# LPCB235_-_SPI_UART_-_GROUP_A.net
KiCad netlist of a schematic drawn in Altium Designer
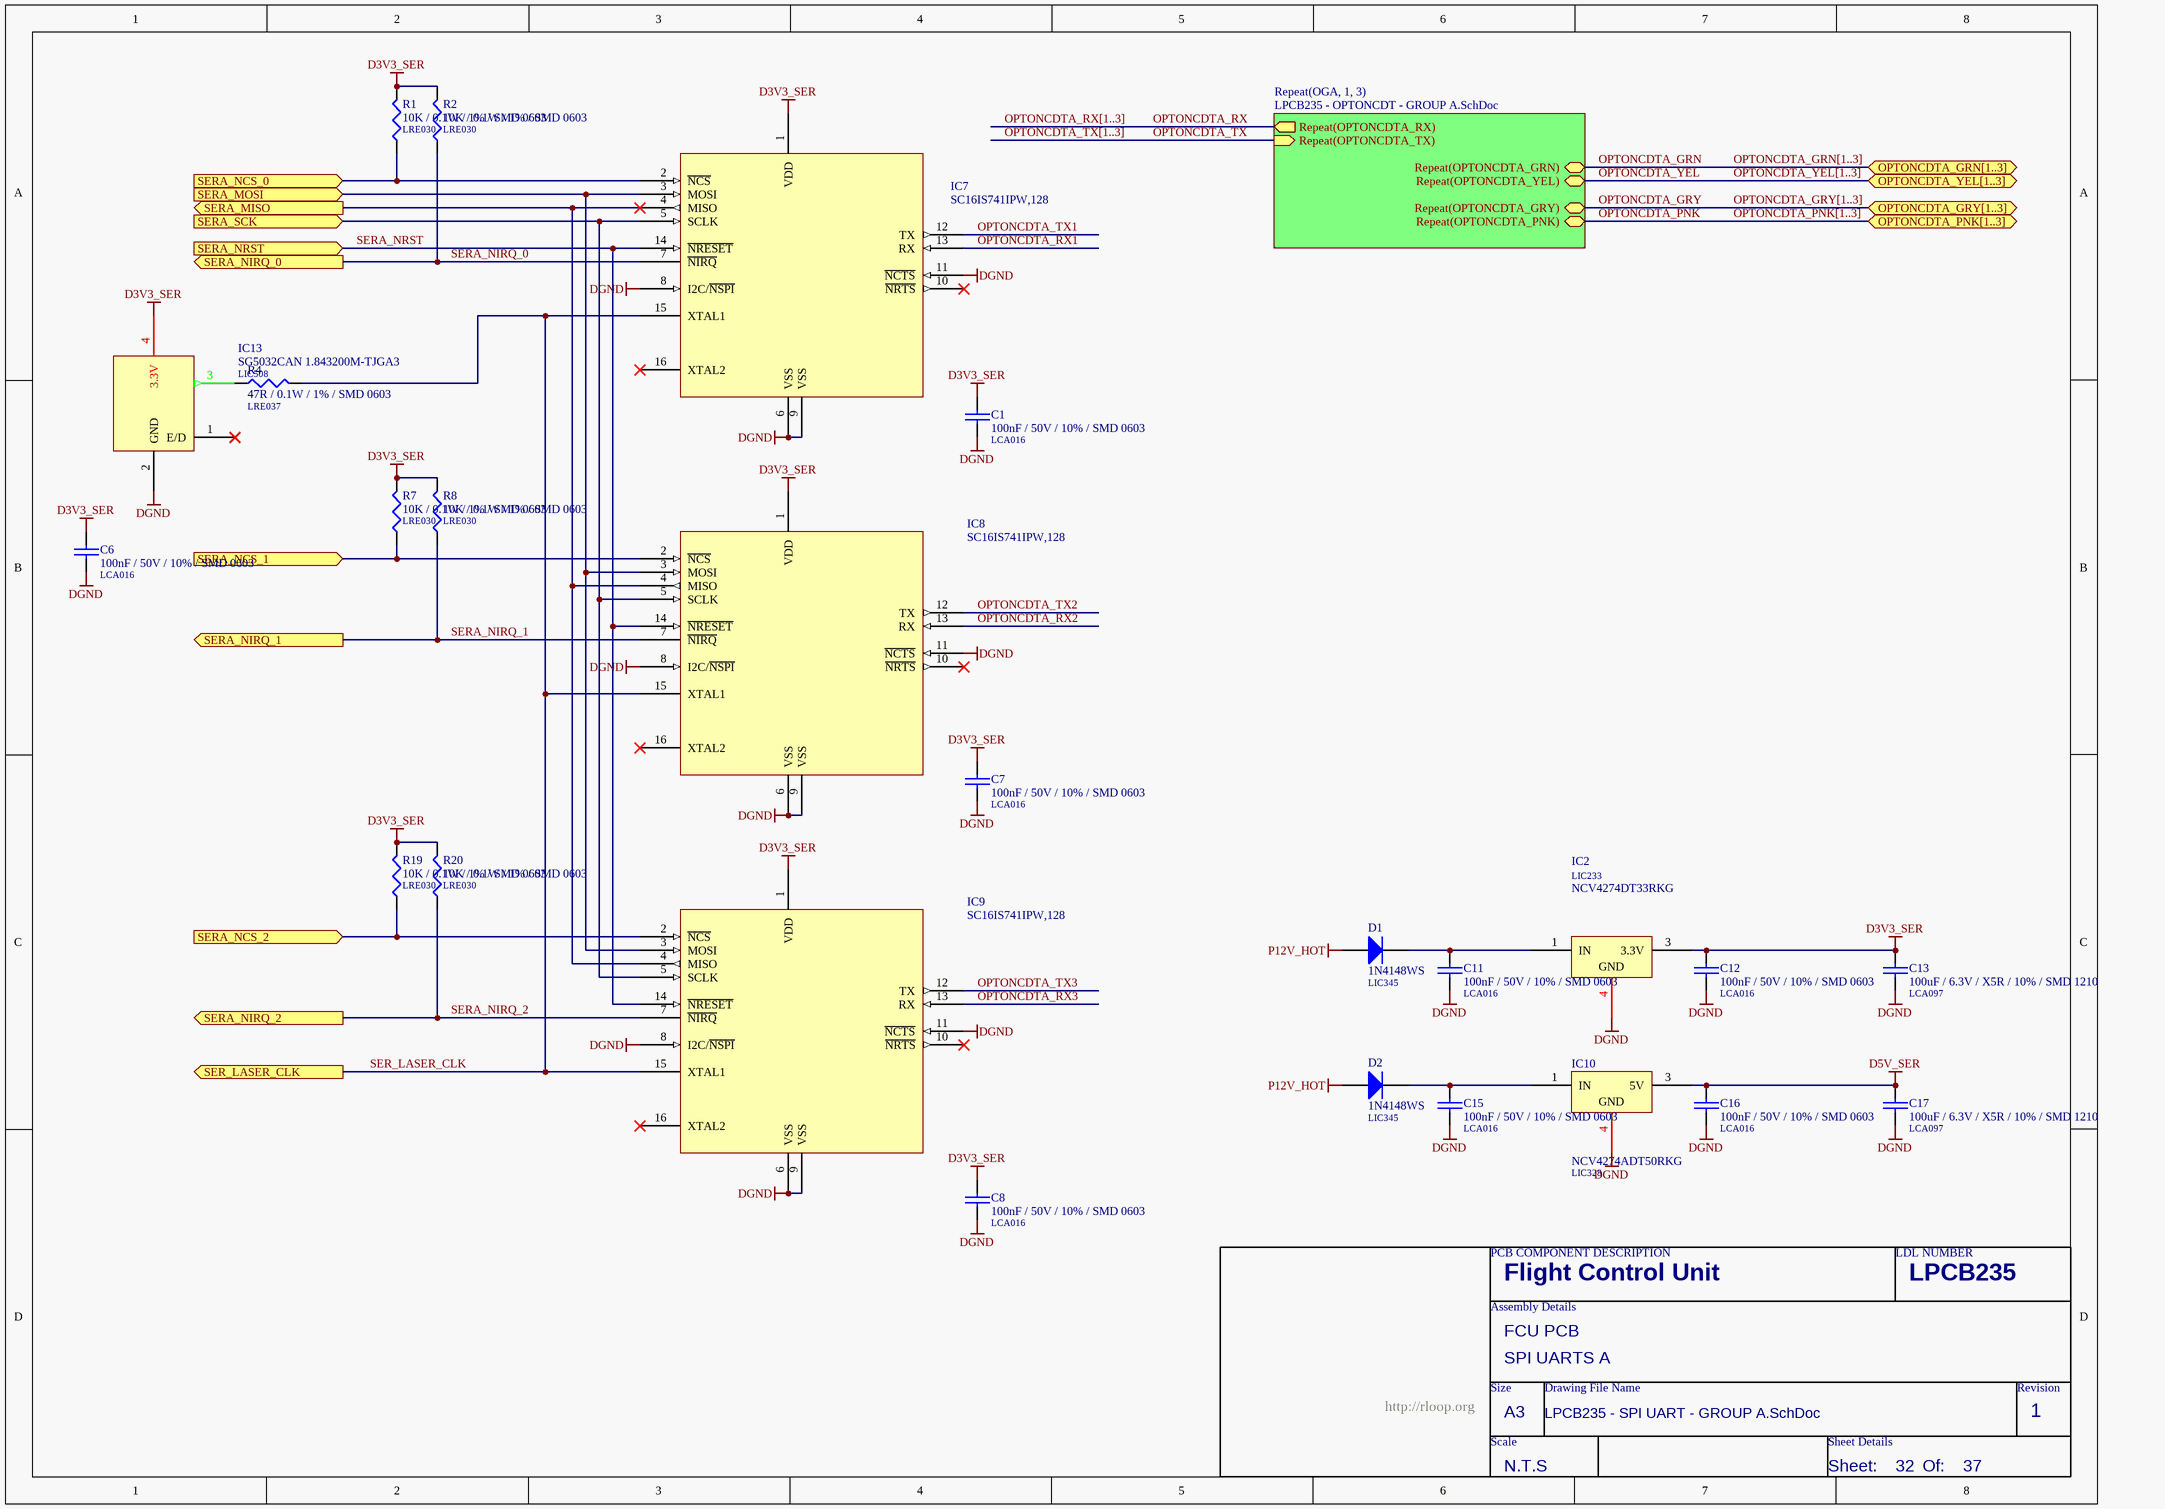
[diagram p0: LPCB235 - SPI UART - GROUP A.SchDoc]

(export (version "E")
  (design (tool "Eeschema 10.0.6"))
  (components
    (comp (ref "C1")
      (value "100nF / 50V / 10% / SMD 0603")
      (footprint "LFP011__CC1608-0603-IPC7351_B")
      (description "Capacitor, Ceramic Chip, 100nF (0.1uF), 50V, 5%, SMD 0603 [LCA016]")
      (fields (field (name "LDL_NUMBER") "LCA016"))
      (libsource (lib "LDL_Capacitors") (part "100nF / 50V / 10% / SMD 0603"))
    )
    (comp (ref "C6")
      (value "100nF / 50V / 10% / SMD 0603")
      (footprint "LFP011__CC1608-0603-IPC7351_B")
      (description "Capacitor, Ceramic Chip, 100nF (0.1uF), 50V, 5%, SMD 0603 [LCA016]")
      (fields (field (name "LDL_NUMBER") "LCA016"))
      (libsource (lib "LDL_Capacitors") (part "100nF / 50V / 10% / SMD 0603"))
    )
    (comp (ref "C7")
      (value "100nF / 50V / 10% / SMD 0603")
      (footprint "LFP011__CC1608-0603-IPC7351_B")
      (description "Capacitor, Ceramic Chip, 100nF (0.1uF), 50V, 5%, SMD 0603 [LCA016]")
      (fields (field (name "LDL_NUMBER") "LCA016"))
      (libsource (lib "LDL_Capacitors") (part "100nF / 50V / 10% / SMD 0603"))
    )
    (comp (ref "C8")
      (value "100nF / 50V / 10% / SMD 0603")
      (footprint "LFP011__CC1608-0603-IPC7351_B")
      (description "Capacitor, Ceramic Chip, 100nF (0.1uF), 50V, 5%, SMD 0603 [LCA016]")
      (fields (field (name "LDL_NUMBER") "LCA016"))
      (libsource (lib "LDL_Capacitors") (part "100nF / 50V / 10% / SMD 0603"))
    )
    (comp (ref "C11")
      (value "100nF / 50V / 10% / SMD 0603")
      (footprint "LFP011__CC1608-0603-IPC7351_B")
      (description "Capacitor, Ceramic Chip, 100nF (0.1uF), 50V, 5%, SMD 0603 [LCA016]")
      (fields (field (name "LDL_NUMBER") "LCA016"))
      (libsource (lib "LDL_Capacitors") (part "100nF / 50V / 10% / SMD 0603"))
    )
    (comp (ref "C12")
      (value "100nF / 50V / 10% / SMD 0603")
      (footprint "LFP011__CC1608-0603-IPC7351_B")
      (description "Capacitor, Ceramic Chip, 100nF (0.1uF), 50V, 5%, SMD 0603 [LCA016]")
      (fields (field (name "LDL_NUMBER") "LCA016"))
      (libsource (lib "LDL_Capacitors") (part "100nF / 50V / 10% / SMD 0603"))
    )
    (comp (ref "C13")
      (value "100uF / 6.3V / X5R / 10% / SMD 1210")
      (footprint "LFP013__CC3225-1210-IPC7351_B")
      (description "Capacitor, Ceramic Chip, 100uF, 6.3V, X5R, 20%, SMD 1210 [LCA097]")
      (fields (field (name "LDL_NUMBER") "LCA097"))
      (libsource (lib "LDL_Capacitors") (part "100uF / 6.3V / X5R / 10% / SMD 1210"))
    )
    (comp (ref "C15")
      (value "100nF / 50V / 10% / SMD 0603")
      (footprint "LFP011__CC1608-0603-IPC7351_B")
      (description "Capacitor, Ceramic Chip, 100nF (0.1uF), 50V, 5%, SMD 0603 [LCA016]")
      (fields (field (name "LDL_NUMBER") "LCA016"))
      (libsource (lib "LDL_Capacitors") (part "100nF / 50V / 10% / SMD 0603"))
    )
    (comp (ref "C16")
      (value "100nF / 50V / 10% / SMD 0603")
      (footprint "LFP011__CC1608-0603-IPC7351_B")
      (description "Capacitor, Ceramic Chip, 100nF (0.1uF), 50V, 5%, SMD 0603 [LCA016]")
      (fields (field (name "LDL_NUMBER") "LCA016"))
      (libsource (lib "LDL_Capacitors") (part "100nF / 50V / 10% / SMD 0603"))
    )
    (comp (ref "C17")
      (value "100uF / 6.3V / X5R / 10% / SMD 1210")
      (footprint "LFP013__CC3225-1210-IPC7351_B")
      (description "Capacitor, Ceramic Chip, 100uF, 6.3V, X5R, 20%, SMD 1210 [LCA097]")
      (fields (field (name "LDL_NUMBER") "LCA097"))
      (libsource (lib "LDL_Capacitors") (part "100uF / 6.3V / X5R / 10% / SMD 1210"))
    )
    (comp (ref "D1")
      (value "1N4148WS")
      (footprint "LFP001__SOD-323F")
      (description "Diode, Small Signal, SMD SOD-323F [LIC345]")
      (fields (field (name "LDL_NUMBER") "LIC345"))
      (libsource (lib "LDL_Semiconductors") (part "1N4148WS"))
    )
    (comp (ref "D2")
      (value "1N4148WS")
      (footprint "LFP001__SOD-323F")
      (description "Diode, Small Signal, SMD SOD-323F [LIC345]")
      (fields (field (name "LDL_NUMBER") "LIC345"))
      (libsource (lib "LDL_Semiconductors") (part "1N4148WS"))
    )
    (comp (ref "IC2")
      (value "NCV4274DT33RKG")
      (footprint "LFP019__369A-13")
      (description "IC, Voltage Regulator, 400mA, 3.3V LDO, SMD DPAK [LIC233]")
      (fields (field (name "LDL_NUMBER") "LIC233"))
      (libsource (lib "LDL_Semiconductors") (part "NCV4274DT33RKG"))
    )
    (comp (ref "IC7")
      (value "SC16IS741IPW,128")
      (footprint "LFP049__TSSOP-16")
      (description "IC, SPI to UART bridge [LIC472]")
      (libsource (lib "LDL_Semiconductors") (part "SC16IS741IPW,128"))
    )
    (comp (ref "IC8")
      (value "SC16IS741IPW,128")
      (footprint "LFP049__TSSOP-16")
      (description "IC, SPI to UART bridge [LIC472]")
      (libsource (lib "LDL_Semiconductors") (part "SC16IS741IPW,128"))
    )
    (comp (ref "IC9")
      (value "SC16IS741IPW,128")
      (footprint "LFP049__TSSOP-16")
      (description "IC, SPI to UART bridge [LIC472]")
      (libsource (lib "LDL_Semiconductors") (part "SC16IS741IPW,128"))
    )
    (comp (ref "IC10")
      (value "NCV4274ADT50RKG")
      (footprint "LFP019__369A-13")
      (description "IC, Voltage Regulator, 400mA, 5V LDO, SMD DPAK [LIC328]")
      (fields (field (name "LDL_NUMBER") "LIC328"))
      (libsource (lib "LDL_Semiconductors") (part "NCV4274ADT50RKG"))
    )
    (comp (ref "IC13")
      (value "SG5032CAN 1.843200M-TJGA3")
      (footprint "LFP072__ASFLMB")
      (description "IC, Oscillator Module, 1.8432MHz, 3.3V, SMD [LIC508]")
      (fields (field (name "LDL_NUMBER") "LIC508"))
      (libsource (lib "LDL_Semiconductors") (part "SG5032CAN 1.843200M-TJGA3"))
    )
    (comp (ref "R1")
      (value "10K / 0.1W / 1% / SMD 0603")
      (footprint "LFP020__CR1608-0603-IPC7351_B")
      (description "Resistor, Ceramic Chip, 10K, 0.1W, 1%, SMD 0603 [LRE030]")
      (fields (field (name "LDL_NUMBER") "LRE030"))
      (libsource (lib "LDL_Resistors") (part "10K / 0.1W / 1% / SMD 0603"))
    )
    (comp (ref "R2")
      (value "10K / 0.1W / 1% / SMD 0603")
      (footprint "LFP020__CR1608-0603-IPC7351_B")
      (description "Resistor, Ceramic Chip, 10K, 0.1W, 1%, SMD 0603 [LRE030]")
      (fields (field (name "LDL_NUMBER") "LRE030"))
      (libsource (lib "LDL_Resistors") (part "10K / 0.1W / 1% / SMD 0603"))
    )
    (comp (ref "R4")
      (value "47R / 0.1W / 1% / SMD 0603")
      (footprint "LFP020__CR1608-0603-IPC7351_B")
      (description "Resistor, Ceramic Chip, 47R, 0.1W, 1%, SMD 0603 [LRE037]")
      (fields (field (name "LDL_NUMBER") "LRE037"))
      (libsource (lib "LDL_Resistors") (part "47R / 0.1W / 1% / SMD 0603"))
    )
    (comp (ref "R7")
      (value "10K / 0.1W / 1% / SMD 0603")
      (footprint "LFP020__CR1608-0603-IPC7351_B")
      (description "Resistor, Ceramic Chip, 10K, 0.1W, 1%, SMD 0603 [LRE030]")
      (fields (field (name "LDL_NUMBER") "LRE030"))
      (libsource (lib "LDL_Resistors") (part "10K / 0.1W / 1% / SMD 0603"))
    )
    (comp (ref "R8")
      (value "10K / 0.1W / 1% / SMD 0603")
      (footprint "LFP020__CR1608-0603-IPC7351_B")
      (description "Resistor, Ceramic Chip, 10K, 0.1W, 1%, SMD 0603 [LRE030]")
      (fields (field (name "LDL_NUMBER") "LRE030"))
      (libsource (lib "LDL_Resistors") (part "10K / 0.1W / 1% / SMD 0603"))
    )
    (comp (ref "R19")
      (value "10K / 0.1W / 1% / SMD 0603")
      (footprint "LFP020__CR1608-0603-IPC7351_B")
      (description "Resistor, Ceramic Chip, 10K, 0.1W, 1%, SMD 0603 [LRE030]")
      (fields (field (name "LDL_NUMBER") "LRE030"))
      (libsource (lib "LDL_Resistors") (part "10K / 0.1W / 1% / SMD 0603"))
    )
    (comp (ref "R20")
      (value "10K / 0.1W / 1% / SMD 0603")
      (footprint "LFP020__CR1608-0603-IPC7351_B")
      (description "Resistor, Ceramic Chip, 10K, 0.1W, 1%, SMD 0603 [LRE030]")
      (fields (field (name "LDL_NUMBER") "LRE030"))
      (libsource (lib "LDL_Resistors") (part "10K / 0.1W / 1% / SMD 0603"))
    )
  )
  (nets
    (net (code "20") (name "/OPTONCDTA_RX1") (class "Default")
      (node (ref "IC7") (pin "13") (pinfunction "RX_13") (pintype "input"))
    )
    (net (code "21") (name "/OPTONCDTA_RX2") (class "Default")
      (node (ref "IC8") (pin "13") (pinfunction "RX_13") (pintype "input"))
    )
    (net (code "22") (name "/OPTONCDTA_RX3") (class "Default")
      (node (ref "IC9") (pin "13") (pinfunction "RX_13") (pintype "input"))
    )
    (net (code "25") (name "/OPTONCDTA_TX1") (class "Default")
      (node (ref "IC7") (pin "12") (pinfunction "TX_12") (pintype "output"))
    )
    (net (code "26") (name "/OPTONCDTA_TX2") (class "Default")
      (node (ref "IC8") (pin "12") (pinfunction "TX_12") (pintype "output"))
    )
    (net (code "27") (name "/OPTONCDTA_TX3") (class "Default")
      (node (ref "IC9") (pin "12") (pinfunction "TX_12") (pintype "output"))
    )
    (net (code "31") (name "/SERA_MISO") (class "Default")
      (node (ref "IC7") (pin "4") (pinfunction "MISO_4") (pintype "output"))
      (node (ref "IC8") (pin "4") (pinfunction "MISO_4") (pintype "output"))
      (node (ref "IC9") (pin "4") (pinfunction "MISO_4") (pintype "output"))
    )
    (net (code "32") (name "/SERA_MOSI") (class "Default")
      (node (ref "IC7") (pin "3") (pinfunction "MOSI_3") (pintype "input"))
      (node (ref "IC8") (pin "3") (pinfunction "MOSI_3") (pintype "input"))
      (node (ref "IC9") (pin "3") (pinfunction "MOSI_3") (pintype "input"))
    )
    (net (code "33") (name "/SERA_NCS_0") (class "Default")
      (node (ref "IC7") (pin "2") (pinfunction "~{NCS}_2") (pintype "input"))
      (node (ref "R1") (pin "1") (pintype "passive"))
    )
    (net (code "34") (name "/SERA_NCS_1") (class "Default")
      (node (ref "IC8") (pin "2") (pinfunction "~{NCS}_2") (pintype "input"))
      (node (ref "R7") (pin "1") (pintype "passive"))
    )
    (net (code "35") (name "/SERA_NCS_2") (class "Default")
      (node (ref "IC9") (pin "2") (pinfunction "~{NCS}_2") (pintype "input"))
      (node (ref "R19") (pin "1") (pintype "passive"))
    )
    (net (code "36") (name "/SERA_NIRQ_0") (class "Default")
      (node (ref "IC7") (pin "7") (pinfunction "~{NIRQ}_7") (pintype "passive"))
      (node (ref "R2") (pin "1") (pintype "passive"))
    )
    (net (code "37") (name "/SERA_NIRQ_1") (class "Default")
      (node (ref "IC8") (pin "7") (pinfunction "~{NIRQ}_7") (pintype "passive"))
      (node (ref "R8") (pin "1") (pintype "passive"))
    )
    (net (code "38") (name "/SERA_NIRQ_2") (class "Default")
      (node (ref "IC9") (pin "7") (pinfunction "~{NIRQ}_7") (pintype "passive"))
      (node (ref "R20") (pin "1") (pintype "passive"))
    )
    (net (code "39") (name "/SERA_NRST") (class "Default")
      (node (ref "IC7") (pin "14") (pinfunction "~{NRESET}_14") (pintype "input"))
      (node (ref "IC8") (pin "14") (pinfunction "~{NRESET}_14") (pintype "input"))
      (node (ref "IC9") (pin "14") (pinfunction "~{NRESET}_14") (pintype "input"))
    )
    (net (code "40") (name "/SERA_SCK") (class "Default")
      (node (ref "IC7") (pin "5") (pinfunction "SCLK_5") (pintype "input"))
      (node (ref "IC8") (pin "5") (pinfunction "SCLK_5") (pintype "input"))
      (node (ref "IC9") (pin "5") (pinfunction "SCLK_5") (pintype "input"))
    )
    (net (code "41") (name "/SER_LASER_CLK") (class "Default")
      (node (ref "IC7") (pin "15") (pinfunction "XTAL1_15") (pintype "passive"))
      (node (ref "IC8") (pin "15") (pinfunction "XTAL1_15") (pintype "passive"))
      (node (ref "IC9") (pin "15") (pinfunction "XTAL1_15") (pintype "passive"))
      (node (ref "R4") (pin "2") (pintype "passive"))
    )
    (net (code "42") (name "D3V3_SER") (class "Default")
      (node (ref "C1") (pin "1") (pintype "passive"))
      (node (ref "C12") (pin "1") (pintype "passive"))
      (node (ref "C13") (pin "1") (pintype "passive"))
      (node (ref "C6") (pin "1") (pintype "passive"))
      (node (ref "C7") (pin "1") (pintype "passive"))
      (node (ref "C8") (pin "1") (pintype "passive"))
      (node (ref "IC13") (pin "4") (pinfunction "3.3V_4") (pintype "power_in"))
      (node (ref "IC2") (pin "3") (pinfunction "3.3V_3") (pintype "power_in"))
      (node (ref "IC7") (pin "1") (pinfunction "VDD_1") (pintype "power_in"))
      (node (ref "IC8") (pin "1") (pinfunction "VDD_1") (pintype "power_in"))
      (node (ref "IC9") (pin "1") (pinfunction "VDD_1") (pintype "power_in"))
      (node (ref "R1") (pin "2") (pintype "passive"))
      (node (ref "R19") (pin "2") (pintype "passive"))
      (node (ref "R2") (pin "2") (pintype "passive"))
      (node (ref "R20") (pin "2") (pintype "passive"))
      (node (ref "R7") (pin "2") (pintype "passive"))
      (node (ref "R8") (pin "2") (pintype "passive"))
    )
    (net (code "43") (name "D5V_SER") (class "Default")
      (node (ref "C16") (pin "1") (pintype "passive"))
      (node (ref "C17") (pin "1") (pintype "passive"))
      (node (ref "IC10") (pin "3") (pinfunction "5V_3") (pintype "power_in"))
    )
    (net (code "44") (name "DGND") (class "Default")
      (node (ref "C1") (pin "2") (pintype "passive"))
      (node (ref "C11") (pin "2") (pintype "passive"))
      (node (ref "C12") (pin "2") (pintype "passive"))
      (node (ref "C13") (pin "2") (pintype "passive"))
      (node (ref "C15") (pin "2") (pintype "passive"))
      (node (ref "C16") (pin "2") (pintype "passive"))
      (node (ref "C17") (pin "2") (pintype "passive"))
      (node (ref "C6") (pin "2") (pintype "passive"))
      (node (ref "C7") (pin "2") (pintype "passive"))
      (node (ref "C8") (pin "2") (pintype "passive"))
      (node (ref "IC10") (pin "4") (pinfunction "ADJ_4") (pintype "power_in"))
      (node (ref "IC13") (pin "2") (pinfunction "GND_2") (pintype "power_in"))
      (node (ref "IC2") (pin "4") (pinfunction "GND_4") (pintype "power_in"))
      (node (ref "IC7") (pin "11") (pinfunction "~{NCTS}_11") (pintype "input"))
      (node (ref "IC7") (pin "6") (pinfunction "VSS_6") (pintype "power_in"))
      (node (ref "IC7") (pin "8") (pinfunction "I2C/~{NSPI}_8") (pintype "input"))
      (node (ref "IC7") (pin "9") (pinfunction "VSS_9") (pintype "power_in"))
      (node (ref "IC8") (pin "11") (pinfunction "~{NCTS}_11") (pintype "input"))
      (node (ref "IC8") (pin "6") (pinfunction "VSS_6") (pintype "power_in"))
      (node (ref "IC8") (pin "8") (pinfunction "I2C/~{NSPI}_8") (pintype "input"))
      (node (ref "IC8") (pin "9") (pinfunction "VSS_9") (pintype "power_in"))
      (node (ref "IC9") (pin "11") (pinfunction "~{NCTS}_11") (pintype "input"))
      (node (ref "IC9") (pin "6") (pinfunction "VSS_6") (pintype "power_in"))
      (node (ref "IC9") (pin "8") (pinfunction "I2C/~{NSPI}_8") (pintype "input"))
      (node (ref "IC9") (pin "9") (pinfunction "VSS_9") (pintype "power_in"))
    )
    (net (code "45") (name "Net-(D1-K)") (class "Default")
      (node (ref "C11") (pin "1") (pintype "passive"))
      (node (ref "D1") (pin "1") (pinfunction "K_1") (pintype "passive"))
      (node (ref "IC2") (pin "1") (pinfunction "IN_1") (pintype "power_in"))
    )
    (net (code "46") (name "Net-(D2-K)") (class "Default")
      (node (ref "C15") (pin "1") (pintype "passive"))
      (node (ref "D2") (pin "1") (pinfunction "K_1") (pintype "passive"))
      (node (ref "IC10") (pin "1") (pinfunction "IN_1") (pintype "power_in"))
    )
    (net (code "47") (name "Net-(IC13-OUT)") (class "Default")
      (node (ref "IC13") (pin "3") (pinfunction "OUT_3") (pintype "output"))
      (node (ref "R4") (pin "1") (pintype "passive"))
    )
    (net (code "48") (name "P12V_HOT") (class "Default")
      (node (ref "D1") (pin "2") (pinfunction "A_2") (pintype "passive"))
      (node (ref "D2") (pin "2") (pinfunction "A_2") (pintype "passive"))
    )
    (net (code "49") (name "unconnected-(IC7-XTAL2-Pad16)") (class "Default")
      (node (ref "IC7") (pin "16") (pinfunction "XTAL2_16") (pintype "passive+no_connect"))
    )
    (net (code "50") (name "unconnected-(IC7-~{NRTS}-Pad10)") (class "Default")
      (node (ref "IC7") (pin "10") (pinfunction "~{NRTS}_10") (pintype "output+no_connect"))
    )
    (net (code "51") (name "unconnected-(IC8-XTAL2-Pad16)") (class "Default")
      (node (ref "IC8") (pin "16") (pinfunction "XTAL2_16") (pintype "passive+no_connect"))
    )
    (net (code "52") (name "unconnected-(IC8-~{NRTS}-Pad10)") (class "Default")
      (node (ref "IC8") (pin "10") (pinfunction "~{NRTS}_10") (pintype "output+no_connect"))
    )
    (net (code "53") (name "unconnected-(IC9-XTAL2-Pad16)") (class "Default")
      (node (ref "IC9") (pin "16") (pinfunction "XTAL2_16") (pintype "passive+no_connect"))
    )
    (net (code "54") (name "unconnected-(IC9-~{NRTS}-Pad10)") (class "Default")
      (node (ref "IC9") (pin "10") (pinfunction "~{NRTS}_10") (pintype "output+no_connect"))
    )
    (net (code "55") (name "unconnected-(IC13-E{slash}D-Pad1)") (class "Default")
      (node (ref "IC13") (pin "1") (pinfunction "E/D_1") (pintype "passive+no_connect"))
    )
  )
)
